# G624C.net
KiCad netlist of a schematic drawn in EAGLE
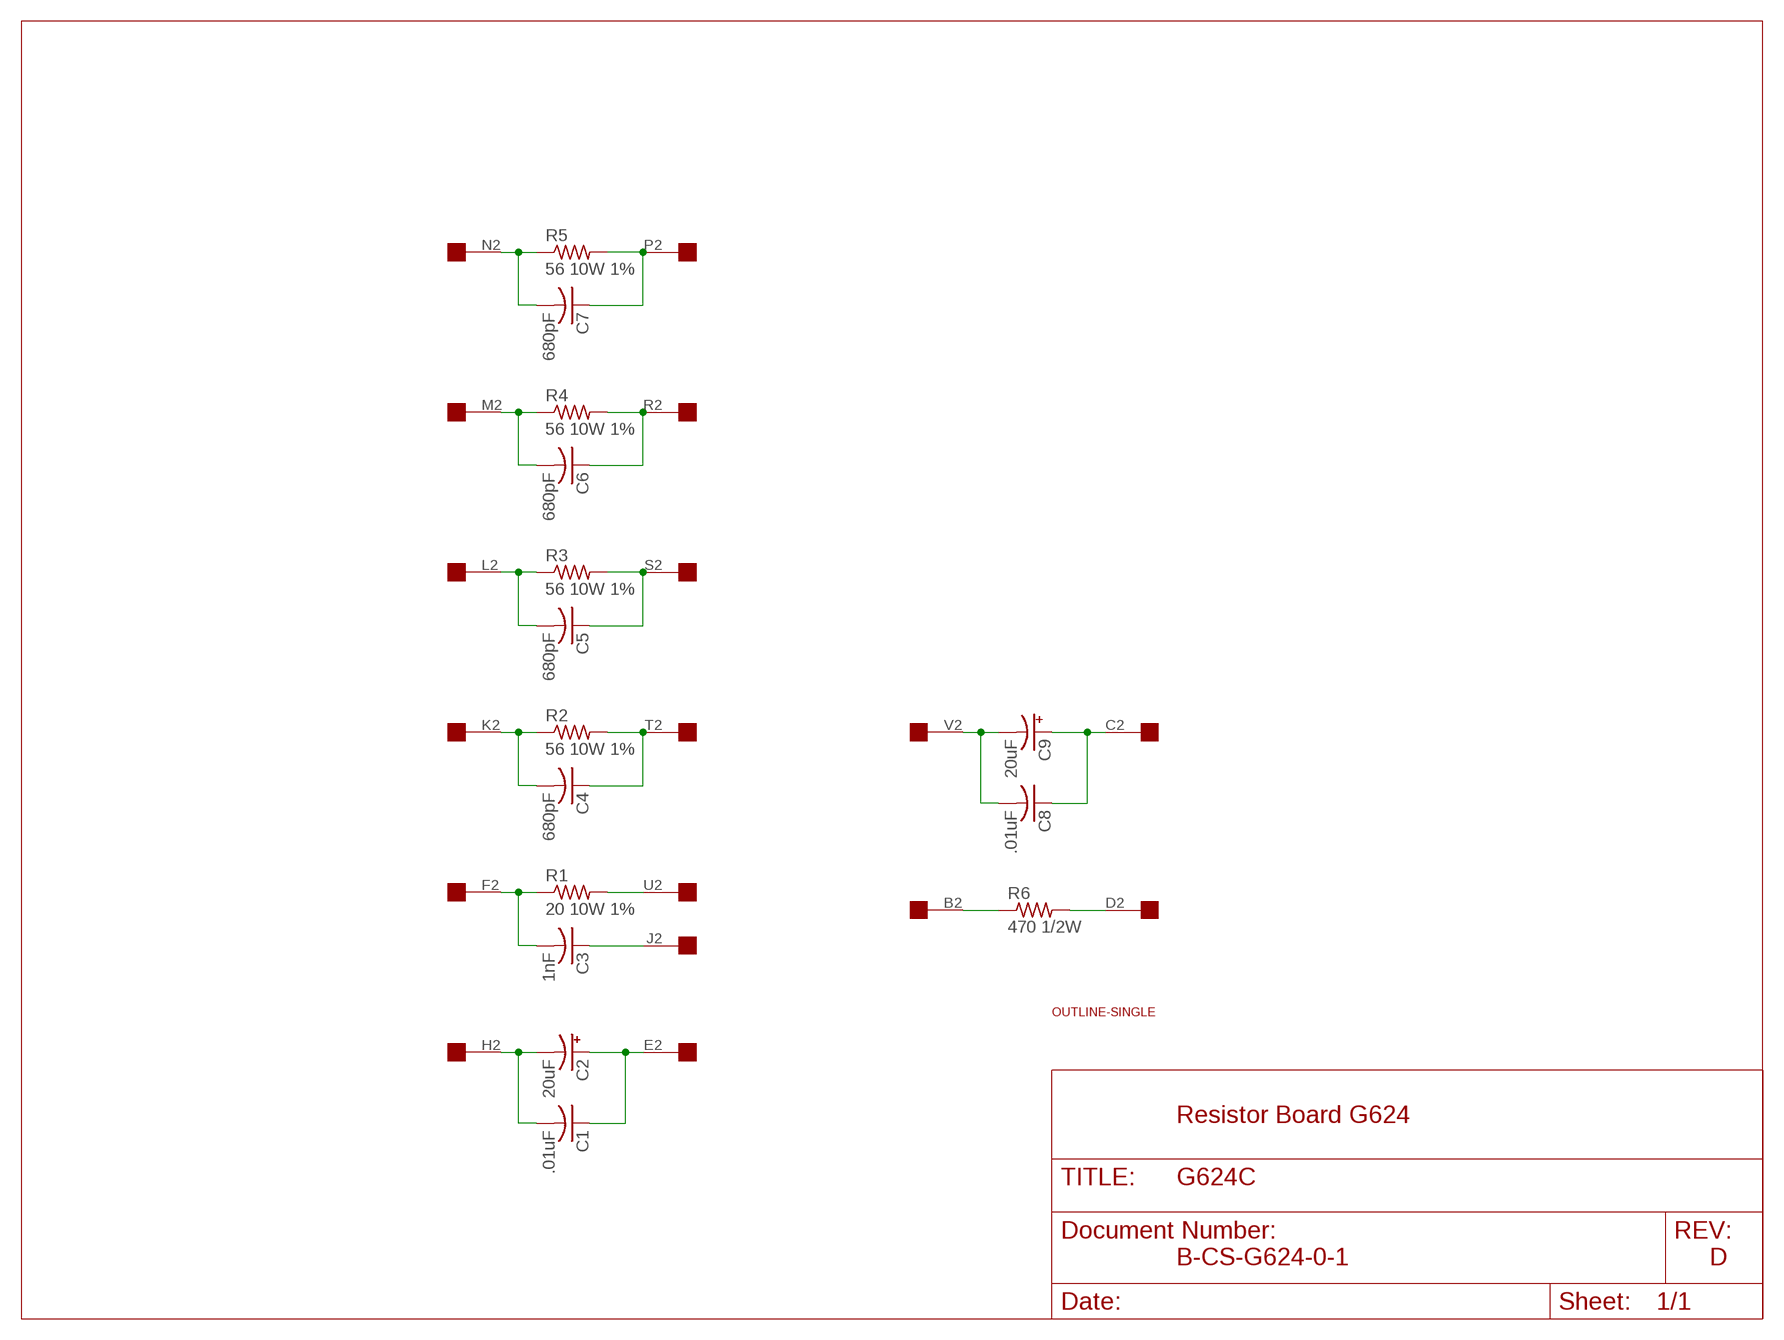
[diagram p0: schematic, sheet 1]

(export (version "E")
  (design (tool "Eeschema 10.0.6"))
  (components
    (comp (ref "C1")
      (value ".01uF")
      (footprint "eagle-import:C050-025X075")
      (libsource (lib "eagle-import") (part "C-US050-025X075"))
    )
    (comp (ref "C2")
      (value "20uF")
      (footprint "eagle-import:E28-8")
      (libsource (lib "eagle-import") (part "CPOL-USE28-8AXIAL"))
    )
    (comp (ref "C3")
      (value "1nF")
      (footprint "eagle-import:C050-025X075")
      (libsource (lib "eagle-import") (part "C-US050-025X075"))
    )
    (comp (ref "C4")
      (value "680pF")
      (footprint "eagle-import:C150-054X183")
      (libsource (lib "eagle-import") (part "C-US150-054X183"))
    )
    (comp (ref "C5")
      (value "680pF")
      (footprint "eagle-import:C150-054X183")
      (libsource (lib "eagle-import") (part "C-US150-054X183"))
    )
    (comp (ref "C6")
      (value "680pF")
      (footprint "eagle-import:C050-025X075")
      (libsource (lib "eagle-import") (part "C-US050-025X075"))
    )
    (comp (ref "C7")
      (value "680pF")
      (footprint "eagle-import:C050-025X075")
      (libsource (lib "eagle-import") (part "C-US050-025X075"))
    )
    (comp (ref "C8")
      (value ".01uF")
      (footprint "eagle-import:C050-025X075")
      (libsource (lib "eagle-import") (part "C-US050-025X075"))
    )
    (comp (ref "C9")
      (value "20uF")
      (footprint "eagle-import:E28-8")
      (libsource (lib "eagle-import") (part "CPOL-USE28-8AXIAL"))
    )
    (comp (ref "R1")
      (value "20 10W 1%")
      (footprint "eagle-import:0944_51")
      (libsource (lib "eagle-import") (part "R-US_0944/51"))
    )
    (comp (ref "R2")
      (value "56 10W 1%")
      (footprint "eagle-import:0944_51")
      (libsource (lib "eagle-import") (part "R-US_0944/51"))
    )
    (comp (ref "R3")
      (value "56 10W 1%")
      (footprint "eagle-import:0944_51")
      (libsource (lib "eagle-import") (part "R-US_0944/51"))
    )
    (comp (ref "R4")
      (value "56 10W 1%")
      (footprint "eagle-import:0944_51")
      (libsource (lib "eagle-import") (part "R-US_0944/51"))
    )
    (comp (ref "R5")
      (value "56 10W 1%")
      (footprint "eagle-import:0944_51")
      (libsource (lib "eagle-import") (part "R-US_0944/51"))
    )
    (comp (ref "R6")
      (value "470 1/2W")
      (footprint "eagle-import:0411_15")
      (libsource (lib "eagle-import") (part "R-US_0411/15"))
    )
    (comp (ref "U$1")
      (value "EDGE-1")
      (footprint "eagle-import:EDGE-CON1")
      (libsource (lib "eagle-import") (part "EDGE-1"))
    )
    (comp (ref "U$2")
      (value "OUTLINE-SINGLE")
      (footprint "eagle-import:SINGLE")
      (libsource (lib "eagle-import") (part "OUTLINE-SINGLE"))
    )
  )
  (nets
    (net (code "1") (name "Net-(U$1B-1)") (class "Default")
      (node (ref "R6") (pin "1") (pinfunction "1_1") (pintype "passive"))
      (node (ref "U$1") (pin "B2") (pinfunction "1_B2") (pintype "bidirectional"))
    )
    (net (code "2") (name "Net-(U$1C-1)") (class "Default")
      (node (ref "C8") (pin "1") (pinfunction "1_1") (pintype "passive"))
      (node (ref "C9") (pin "+") (pinfunction "+_+") (pintype "passive"))
      (node (ref "U$1") (pin "C2") (pinfunction "1_C2") (pintype "bidirectional"))
    )
    (net (code "3") (name "Net-(U$1D-1)") (class "Default")
      (node (ref "R6") (pin "2") (pinfunction "2_2") (pintype "passive"))
      (node (ref "U$1") (pin "D2") (pinfunction "1_D2") (pintype "bidirectional"))
    )
    (net (code "4") (name "Net-(U$1E-1)") (class "Default")
      (node (ref "C1") (pin "1") (pinfunction "1_1") (pintype "passive"))
      (node (ref "C2") (pin "+") (pinfunction "+_+") (pintype "passive"))
      (node (ref "U$1") (pin "E2") (pinfunction "1_E2") (pintype "bidirectional"))
    )
    (net (code "5") (name "Net-(U$1F-1)") (class "Default")
      (node (ref "C3") (pin "2") (pinfunction "2_2") (pintype "passive"))
      (node (ref "R1") (pin "1") (pinfunction "1_1") (pintype "passive"))
      (node (ref "U$1") (pin "F2") (pinfunction "1_F2") (pintype "bidirectional"))
    )
    (net (code "6") (name "Net-(U$1G-1)") (class "Default")
      (node (ref "C1") (pin "2") (pinfunction "2_2") (pintype "passive"))
      (node (ref "C2") (pin "-") (pinfunction "-_-") (pintype "passive"))
      (node (ref "U$1") (pin "H2") (pinfunction "1_H2") (pintype "bidirectional"))
    )
    (net (code "7") (name "Net-(U$1H-1)") (class "Default")
      (node (ref "C3") (pin "1") (pinfunction "1_1") (pintype "passive"))
      (node (ref "U$1") (pin "J2") (pinfunction "1_J2") (pintype "bidirectional"))
    )
    (net (code "8") (name "Net-(U$1I-1)") (class "Default")
      (node (ref "C4") (pin "2") (pinfunction "2_2") (pintype "passive"))
      (node (ref "R2") (pin "1") (pinfunction "1_1") (pintype "passive"))
      (node (ref "U$1") (pin "K2") (pinfunction "1_K2") (pintype "bidirectional"))
    )
    (net (code "9") (name "Net-(U$1J-1)") (class "Default")
      (node (ref "C5") (pin "2") (pinfunction "2_2") (pintype "passive"))
      (node (ref "R3") (pin "1") (pinfunction "1_1") (pintype "passive"))
      (node (ref "U$1") (pin "L2") (pinfunction "1_L2") (pintype "bidirectional"))
    )
    (net (code "10") (name "Net-(U$1K-1)") (class "Default")
      (node (ref "C6") (pin "2") (pinfunction "2_2") (pintype "passive"))
      (node (ref "R4") (pin "1") (pinfunction "1_1") (pintype "passive"))
      (node (ref "U$1") (pin "M2") (pinfunction "1_M2") (pintype "bidirectional"))
    )
    (net (code "11") (name "Net-(U$1L-1)") (class "Default")
      (node (ref "C7") (pin "2") (pinfunction "2_2") (pintype "passive"))
      (node (ref "R5") (pin "1") (pinfunction "1_1") (pintype "passive"))
      (node (ref "U$1") (pin "N2") (pinfunction "1_N2") (pintype "bidirectional"))
    )
    (net (code "12") (name "Net-(U$1M-1)") (class "Default")
      (node (ref "C7") (pin "1") (pinfunction "1_1") (pintype "passive"))
      (node (ref "R5") (pin "2") (pinfunction "2_2") (pintype "passive"))
      (node (ref "U$1") (pin "P2") (pinfunction "1_P2") (pintype "bidirectional"))
    )
    (net (code "13") (name "Net-(U$1N-1)") (class "Default")
      (node (ref "C6") (pin "1") (pinfunction "1_1") (pintype "passive"))
      (node (ref "R4") (pin "2") (pinfunction "2_2") (pintype "passive"))
      (node (ref "U$1") (pin "R2") (pinfunction "1_R2") (pintype "bidirectional"))
    )
    (net (code "14") (name "Net-(U$1O-1)") (class "Default")
      (node (ref "C5") (pin "1") (pinfunction "1_1") (pintype "passive"))
      (node (ref "R3") (pin "2") (pinfunction "2_2") (pintype "passive"))
      (node (ref "U$1") (pin "S2") (pinfunction "1_S2") (pintype "bidirectional"))
    )
    (net (code "15") (name "Net-(U$1P-1)") (class "Default")
      (node (ref "C4") (pin "1") (pinfunction "1_1") (pintype "passive"))
      (node (ref "R2") (pin "2") (pinfunction "2_2") (pintype "passive"))
      (node (ref "U$1") (pin "T2") (pinfunction "1_T2") (pintype "bidirectional"))
    )
    (net (code "16") (name "Net-(U$1Q-1)") (class "Default")
      (node (ref "R1") (pin "2") (pinfunction "2_2") (pintype "passive"))
      (node (ref "U$1") (pin "U2") (pinfunction "1_U2") (pintype "bidirectional"))
    )
    (net (code "17") (name "Net-(U$1R-1)") (class "Default")
      (node (ref "C8") (pin "2") (pinfunction "2_2") (pintype "passive"))
      (node (ref "C9") (pin "-") (pinfunction "-_-") (pintype "passive"))
      (node (ref "U$1") (pin "V2") (pinfunction "1_V2") (pintype "bidirectional"))
    )
  )
)
